# Kirt-SMD.net
KiCad netlist of a schematic drawn in EAGLE
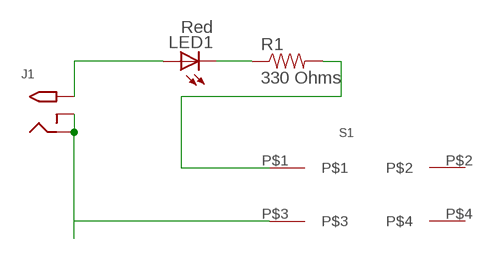
[diagram p0: schematic, sheet 1]

(export (version "E")
  (design (tool "Eeschema 10.0.6"))
  (components
    (comp (ref "J1")
      (value "2.1MMJACKTHM")
      (footprint "eagle-import:PJ-102A")
      (libsource (lib "eagle-import") (part "2.1MMJACKTHM"))
    )
    (comp (ref "LED1")
      (value "Red")
      (footprint "eagle-import:LED5MM")
      (libsource (lib "eagle-import") (part "LED5MM"))
    )
    (comp (ref "R1")
      (value "330 Ohms")
      (footprint "eagle-import:AXIAL-0.3")
      (libsource (lib "eagle-import") (part "RESISTORAXIAL-0.3"))
    )
    (comp (ref "S1")
      (value "BUTTON-TACTILE-SMD")
      (footprint "eagle-import:BUTTON-TACTILE-SMD")
      (libsource (lib "eagle-import") (part "BUTTON-TACTILE-SMD"))
    )
  )
  (nets
    (net (code "1") (name "Net-(J1-PadRING)") (class "Default")
      (node (ref "J1") (pin "RING") (pinfunction "RING_RING") (pintype "bidirectional"))
      (node (ref "J1") (pin "RING_SW") (pinfunction "RING_SW_RING_SW") (pintype "bidirectional"))
      (node (ref "S1") (pin "P$3") (pinfunction "P$3_P$3") (pintype "bidirectional"))
    )
    (net (code "2") (name "Net-(J1-PadTIP)") (class "Default")
      (node (ref "J1") (pin "TIP") (pinfunction "TIP_TIP") (pintype "bidirectional"))
      (node (ref "LED1") (pin "A") (pinfunction "A_A") (pintype "passive"))
    )
    (net (code "3") (name "Net-(LED1-C)") (class "Default")
      (node (ref "LED1") (pin "K") (pinfunction "C_K") (pintype "passive"))
      (node (ref "R1") (pin "P$1") (pinfunction "1_P$1") (pintype "passive"))
    )
    (net (code "4") (name "Net-(R1-2)") (class "Default")
      (node (ref "R1") (pin "P$2") (pinfunction "2_P$2") (pintype "passive"))
      (node (ref "S1") (pin "P$1") (pinfunction "P$1_P$1") (pintype "bidirectional"))
    )
    (net (code "5") (name "unconnected-(S1-PadP$2)") (class "Default")
      (node (ref "S1") (pin "P$2") (pinfunction "P$2_P$2") (pintype "bidirectional"))
    )
    (net (code "6") (name "unconnected-(S1-PadP$4)") (class "Default")
      (node (ref "S1") (pin "P$4") (pinfunction "P$4_P$4") (pintype "bidirectional"))
    )
  )
)
